# TopLevel.net
KiCad netlist of a schematic drawn in Altium Designer
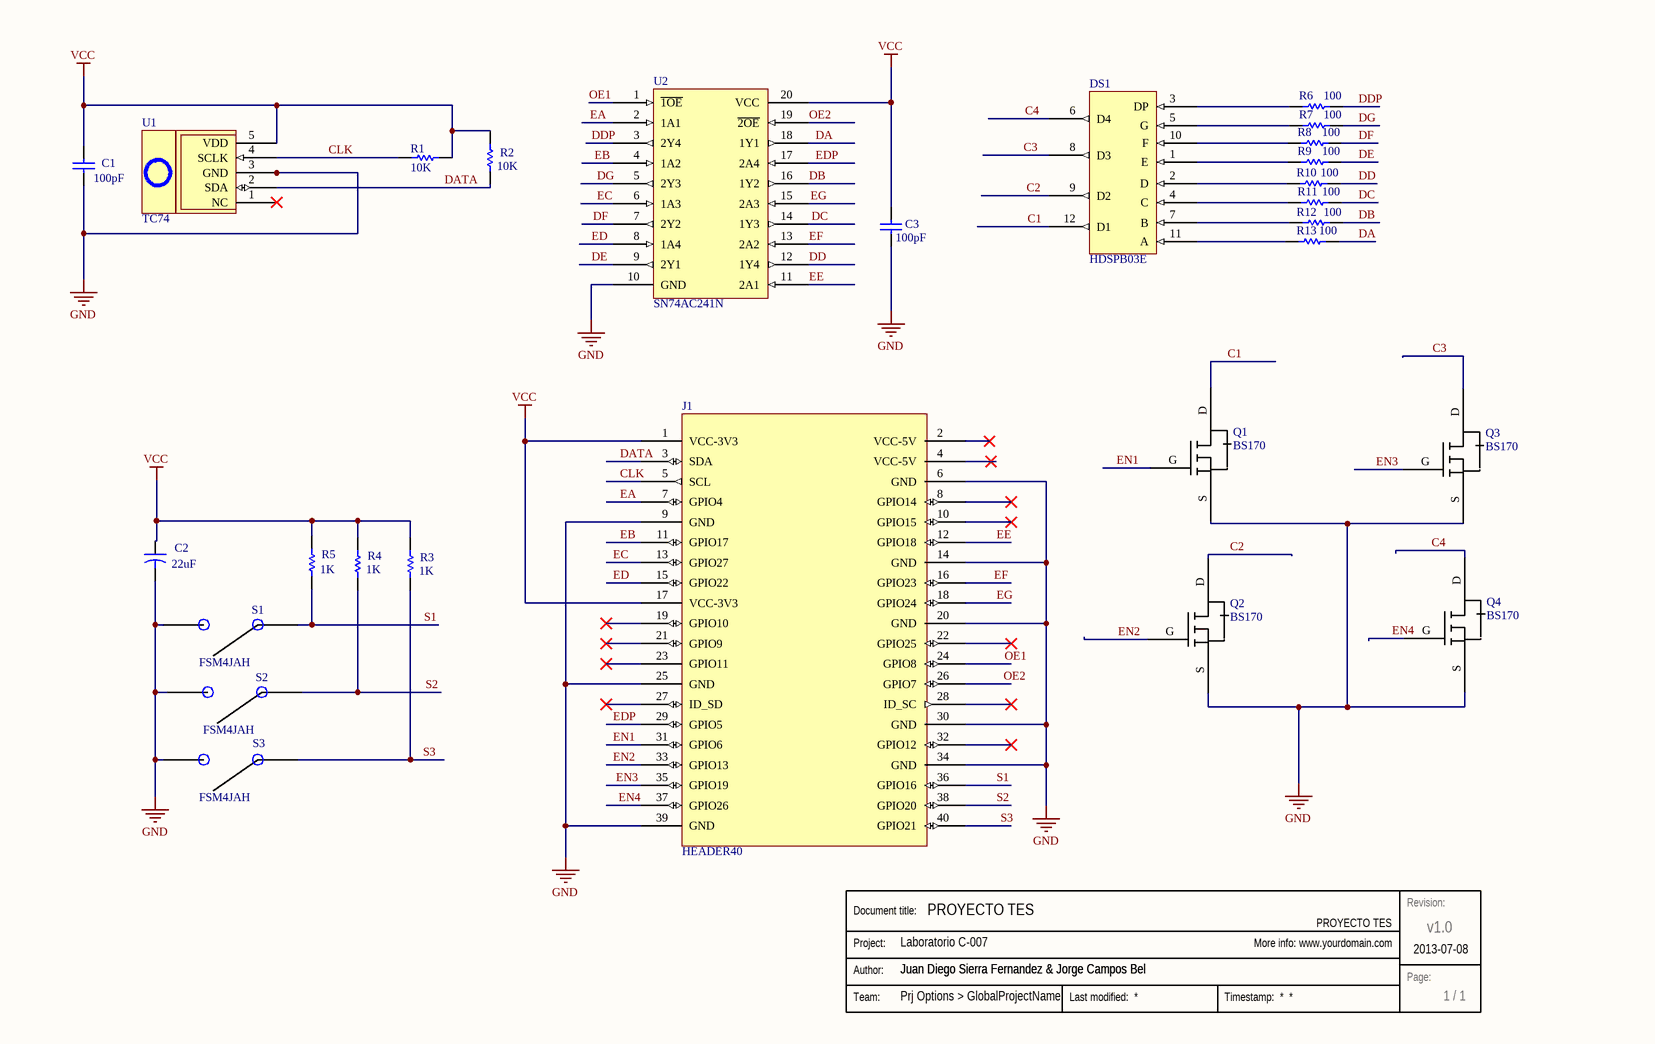
[diagram p0: TopLevel.SchDoc]

(export (version "E")
  (design (tool "Eeschema 10.0.6"))
  (components
    (comp (ref "C1")
      (value "100pF")
      (footprint "RAD-0.3")
      (description "Capacitor")
      (fields (field (name "Comment") "Cap") (field (name "PUBLISHER") "Altium Limited"))
      (libsource (lib "EM") (part "Cap"))
    )
    (comp (ref "C2")
      (value "22uF")
      (footprint "CAPR5-4X5")
      (description "Capacitor")
      (fields (field (name "Comment") "Cap2") (field (name "PUBLISHER") "Altium Limited"))
      (libsource (lib "EM") (part "Cap2"))
    )
    (comp (ref "C3")
      (value "100pF")
      (footprint "RAD-0.3")
      (description "Capacitor")
      (fields (field (name "Comment") "Cap") (field (name "PUBLISHER") "Altium Limited"))
      (libsource (lib "EM") (part "Cap"))
    )
    (comp (ref "DS1")
      (value "HDSPB03E")
      (footprint "DISPLAY")
      (description "Display")
      (libsource (lib "EM") (part "HDSPB03E"))
    )
    (comp (ref "J1")
      (value "HEADER40")
      (footprint "DIP40")
      (description "Header")
      (libsource (lib "EM") (part "HEADER40"))
    )
    (comp (ref "Q1")
      (value "BS170")
      (footprint "MOSFET")
      (description "Mosfet")
      (libsource (lib "EM") (part "BS170"))
    )
    (comp (ref "Q2")
      (value "BS170")
      (footprint "MOSFET")
      (description "Mosfet")
      (libsource (lib "EM") (part "BS170"))
    )
    (comp (ref "Q3")
      (value "BS170")
      (footprint "MOSFET")
      (description "Mosfet")
      (libsource (lib "EM") (part "BS170"))
    )
    (comp (ref "Q4")
      (value "BS170")
      (footprint "MOSFET")
      (description "Mosfet")
      (libsource (lib "EM") (part "BS170"))
    )
    (comp (ref "R1")
      (value "10K")
      (footprint "AXIAL-0.3")
      (description "Resistor")
      (fields (field (name "Comment") "Res1") (field (name "PUBLISHER") "Altium Limited"))
      (libsource (lib "EM") (part "Res1"))
    )
    (comp (ref "R2")
      (value "10K")
      (footprint "AXIAL-0.3")
      (description "Resistor")
      (fields (field (name "Comment") "Res1") (field (name "PUBLISHER") "Altium Limited"))
      (libsource (lib "EM") (part "Res1"))
    )
    (comp (ref "R3")
      (value "1K")
      (footprint "AXIAL-0.3")
      (description "Resistor")
      (fields (field (name "Comment") "Res1") (field (name "PUBLISHER") "Altium Limited"))
      (libsource (lib "EM") (part "Res1"))
    )
    (comp (ref "R4")
      (value "1K")
      (footprint "AXIAL-0.3")
      (description "Resistor")
      (fields (field (name "Comment") "Res1") (field (name "PUBLISHER") "Altium Limited"))
      (libsource (lib "EM") (part "Res1"))
    )
    (comp (ref "R5")
      (value "1K")
      (footprint "AXIAL-0.3")
      (description "Resistor")
      (fields (field (name "Comment") "Res1") (field (name "PUBLISHER") "Altium Limited"))
      (libsource (lib "EM") (part "Res1"))
    )
    (comp (ref "R6")
      (value "100")
      (footprint "AXIAL-0.3")
      (description "Resistor")
      (fields (field (name "Comment") "Res1") (field (name "PUBLISHER") "Altium Limited"))
      (libsource (lib "EM") (part "Res1"))
    )
    (comp (ref "R7")
      (value "100")
      (footprint "AXIAL-0.3")
      (description "Resistor")
      (fields (field (name "Comment") "Res1") (field (name "PUBLISHER") "Altium Limited"))
      (libsource (lib "EM") (part "Res1"))
    )
    (comp (ref "R8")
      (value "100")
      (footprint "AXIAL-0.3")
      (description "Resistor")
      (fields (field (name "Comment") "Res1") (field (name "PUBLISHER") "Altium Limited"))
      (libsource (lib "EM") (part "Res1"))
    )
    (comp (ref "R9")
      (value "100")
      (footprint "AXIAL-0.3")
      (description "Resistor")
      (fields (field (name "Comment") "Res1") (field (name "PUBLISHER") "Altium Limited"))
      (libsource (lib "EM") (part "Res1"))
    )
    (comp (ref "R10")
      (value "100")
      (footprint "AXIAL-0.3")
      (description "Resistor")
      (fields (field (name "Comment") "Res1") (field (name "PUBLISHER") "Altium Limited"))
      (libsource (lib "EM") (part "Res1"))
    )
    (comp (ref "R11")
      (value "100")
      (footprint "AXIAL-0.3")
      (description "Resistor")
      (fields (field (name "Comment") "Res1") (field (name "PUBLISHER") "Altium Limited"))
      (libsource (lib "EM") (part "Res1"))
    )
    (comp (ref "R12")
      (value "100")
      (footprint "AXIAL-0.3")
      (description "Resistor")
      (fields (field (name "Comment") "Res1") (field (name "PUBLISHER") "Altium Limited"))
      (libsource (lib "EM") (part "Res1"))
    )
    (comp (ref "R13")
      (value "100")
      (footprint "AXIAL-0.3")
      (description "Resistor")
      (fields (field (name "Comment") "Res1") (field (name "PUBLISHER") "Altium Limited"))
      (libsource (lib "EM") (part "Res1"))
    )
    (comp (ref "S1")
      (value "FSM4JAH")
      (footprint "SPST")
      (description "Switch")
      (libsource (lib "EM") (part "FSM4JAH"))
    )
    (comp (ref "S2")
      (value "FSM4JAH")
      (footprint "SPST")
      (description "Switch")
      (libsource (lib "EM") (part "FSM4JAH"))
    )
    (comp (ref "S3")
      (value "FSM4JAH")
      (footprint "SPST")
      (description "Switch")
      (libsource (lib "EM") (part "FSM4JAH"))
    )
    (comp (ref "Stamp") (value "Stamp") (libsource (lib "ShieldsLib") (part "Stamp")))
    (comp (ref "U1")
      (value "TC74")
      (footprint "T0220")
      (description "Sensor")
      (libsource (lib "EM") (part "TC74"))
    )
    (comp (ref "U2")
      (value "SN74AC241N")
      (footprint "SN74")
      (description "Driver")
      (libsource (lib "EM") (part "SN74AC241N"))
    )
  )
  (nets
    (net (code "1") (name "/C1") (class "Default")
      (node (ref "DS1") (pin "12") (pinfunction "D1_12") (pintype "output"))
      (node (ref "Q1") (pin "D") (pinfunction "Drain_D") (pintype "passive"))
    )
    (net (code "2") (name "/C2") (class "Default")
      (node (ref "DS1") (pin "9") (pinfunction "D2_9") (pintype "output"))
      (node (ref "Q2") (pin "D") (pinfunction "Drain_D") (pintype "passive"))
    )
    (net (code "3") (name "/C3") (class "Default")
      (node (ref "DS1") (pin "8") (pinfunction "D3_8") (pintype "output"))
      (node (ref "Q3") (pin "D") (pinfunction "Drain_D") (pintype "passive"))
    )
    (net (code "4") (name "/C4") (class "Default")
      (node (ref "DS1") (pin "6") (pinfunction "D4_6") (pintype "output"))
      (node (ref "Q4") (pin "D") (pinfunction "Drain_D") (pintype "passive"))
    )
    (net (code "5") (name "/CLK") (class "Default")
      (node (ref "J1") (pin "5") (pinfunction "SCL_5") (pintype "output"))
      (node (ref "R1") (pin "2") (pinfunction "2_2") (pintype "passive"))
      (node (ref "U1") (pin "4") (pinfunction "SCLK_4") (pintype "input"))
    )
    (net (code "6") (name "/DA") (class "Default")
      (node (ref "R13") (pin "2") (pinfunction "2_2") (pintype "passive"))
      (node (ref "U2") (pin "18") (pinfunction "1Y1_18") (pintype "output"))
    )
    (net (code "7") (name "/DATA") (class "Default")
      (node (ref "J1") (pin "3") (pinfunction "SDA_3") (pintype "bidirectional"))
      (node (ref "R2") (pin "1") (pinfunction "1_1") (pintype "passive"))
      (node (ref "U1") (pin "2") (pinfunction "SDA_2") (pintype "bidirectional"))
    )
    (net (code "8") (name "/DB") (class "Default")
      (node (ref "R12") (pin "2") (pinfunction "2_2") (pintype "passive"))
      (node (ref "U2") (pin "16") (pinfunction "1Y2_16") (pintype "output"))
    )
    (net (code "9") (name "/DC") (class "Default")
      (node (ref "R11") (pin "2") (pinfunction "2_2") (pintype "passive"))
      (node (ref "U2") (pin "14") (pinfunction "1Y3_14") (pintype "output"))
    )
    (net (code "10") (name "/DD") (class "Default")
      (node (ref "R10") (pin "2") (pinfunction "2_2") (pintype "passive"))
      (node (ref "U2") (pin "12") (pinfunction "1Y4_12") (pintype "output"))
    )
    (net (code "11") (name "/DDP") (class "Default")
      (node (ref "R6") (pin "2") (pinfunction "2_2") (pintype "passive"))
      (node (ref "U2") (pin "3") (pinfunction "2Y4_3") (pintype "output"))
    )
    (net (code "12") (name "/DE") (class "Default")
      (node (ref "R9") (pin "2") (pinfunction "2_2") (pintype "passive"))
      (node (ref "U2") (pin "9") (pinfunction "2Y1_9") (pintype "output"))
    )
    (net (code "13") (name "/DF") (class "Default")
      (node (ref "R8") (pin "2") (pinfunction "2_2") (pintype "passive"))
      (node (ref "U2") (pin "7") (pinfunction "2Y2_7") (pintype "output"))
    )
    (net (code "14") (name "/DG") (class "Default")
      (node (ref "R7") (pin "2") (pinfunction "2_2") (pintype "passive"))
      (node (ref "U2") (pin "5") (pinfunction "2Y3_5") (pintype "output"))
    )
    (net (code "15") (name "/EA") (class "Default")
      (node (ref "J1") (pin "7") (pinfunction "GPIO4_7") (pintype "bidirectional"))
      (node (ref "U2") (pin "2") (pinfunction "1A1_2") (pintype "input"))
    )
    (net (code "16") (name "/EB") (class "Default")
      (node (ref "J1") (pin "11") (pinfunction "GPIO17_11") (pintype "bidirectional"))
      (node (ref "U2") (pin "4") (pinfunction "1A2_4") (pintype "input"))
    )
    (net (code "17") (name "/EC") (class "Default")
      (node (ref "J1") (pin "13") (pinfunction "GPIO27_13") (pintype "bidirectional"))
      (node (ref "U2") (pin "6") (pinfunction "1A3_6") (pintype "input"))
    )
    (net (code "18") (name "/ED") (class "Default")
      (node (ref "J1") (pin "15") (pinfunction "GPIO22_15") (pintype "bidirectional"))
      (node (ref "U2") (pin "8") (pinfunction "1A4_8") (pintype "input"))
    )
    (net (code "19") (name "/EDP") (class "Default")
      (node (ref "J1") (pin "29") (pinfunction "GPIO5_29") (pintype "bidirectional"))
      (node (ref "U2") (pin "17") (pinfunction "2A4_17") (pintype "input"))
    )
    (net (code "20") (name "/EE") (class "Default")
      (node (ref "J1") (pin "12") (pinfunction "GPIO18_12") (pintype "bidirectional"))
      (node (ref "U2") (pin "11") (pinfunction "2A1_11") (pintype "input"))
    )
    (net (code "21") (name "/EF") (class "Default")
      (node (ref "J1") (pin "16") (pinfunction "GPIO23_16") (pintype "bidirectional"))
      (node (ref "U2") (pin "13") (pinfunction "2A2_13") (pintype "input"))
    )
    (net (code "22") (name "/EG") (class "Default")
      (node (ref "J1") (pin "18") (pinfunction "GPIO24_18") (pintype "bidirectional"))
      (node (ref "U2") (pin "15") (pinfunction "2A3_15") (pintype "input"))
    )
    (net (code "23") (name "/EN1") (class "Default")
      (node (ref "J1") (pin "31") (pinfunction "GPIO6_31") (pintype "bidirectional"))
      (node (ref "Q1") (pin "G") (pinfunction "Gate_G") (pintype "passive"))
    )
    (net (code "24") (name "/EN2") (class "Default")
      (node (ref "J1") (pin "33") (pinfunction "GPIO13_33") (pintype "bidirectional"))
      (node (ref "Q2") (pin "G") (pinfunction "Gate_G") (pintype "passive"))
    )
    (net (code "25") (name "/EN3") (class "Default")
      (node (ref "J1") (pin "35") (pinfunction "GPIO19_35") (pintype "bidirectional"))
      (node (ref "Q3") (pin "G") (pinfunction "Gate_G") (pintype "passive"))
    )
    (net (code "26") (name "/EN4") (class "Default")
      (node (ref "J1") (pin "37") (pinfunction "GPIO26_37") (pintype "bidirectional"))
      (node (ref "Q4") (pin "G") (pinfunction "Gate_G") (pintype "passive"))
    )
    (net (code "27") (name "/OE1") (class "Default")
      (node (ref "J1") (pin "24") (pinfunction "GPIO8_24") (pintype "bidirectional"))
      (node (ref "U2") (pin "1") (pinfunction "~{1OE}_1") (pintype "input"))
    )
    (net (code "28") (name "/OE2") (class "Default")
      (node (ref "J1") (pin "26") (pinfunction "GPIO7_26") (pintype "bidirectional"))
      (node (ref "U2") (pin "19") (pinfunction "~{2OE}_19") (pintype "input"))
    )
    (net (code "29") (name "/S1") (class "Default")
      (node (ref "J1") (pin "36") (pinfunction "GPIO16_36") (pintype "bidirectional"))
      (node (ref "R5") (pin "1") (pinfunction "1_1") (pintype "passive"))
      (node (ref "S1") (pin "1") (pinfunction "1_1") (pintype "passive"))
    )
    (net (code "30") (name "/S2") (class "Default")
      (node (ref "J1") (pin "38") (pinfunction "GPIO20_38") (pintype "bidirectional"))
      (node (ref "R4") (pin "1") (pinfunction "1_1") (pintype "passive"))
      (node (ref "S2") (pin "1") (pinfunction "1_1") (pintype "passive"))
    )
    (net (code "31") (name "/S3") (class "Default")
      (node (ref "J1") (pin "40") (pinfunction "GPIO21_40") (pintype "bidirectional"))
      (node (ref "R3") (pin "1") (pinfunction "1_1") (pintype "passive"))
      (node (ref "S3") (pin "1") (pinfunction "1_1") (pintype "passive"))
    )
    (net (code "32") (name "GND") (class "Default")
      (node (ref "C1") (pin "1") (pinfunction "1_1") (pintype "passive"))
      (node (ref "C2") (pin "2") (pinfunction "2_2") (pintype "passive"))
      (node (ref "C3") (pin "1") (pinfunction "1_1") (pintype "passive"))
      (node (ref "J1") (pin "14") (pinfunction "GND_14") (pintype "passive"))
      (node (ref "J1") (pin "20") (pinfunction "GND_20") (pintype "passive"))
      (node (ref "J1") (pin "25") (pinfunction "GND_25") (pintype "passive"))
      (node (ref "J1") (pin "30") (pinfunction "GND_30") (pintype "passive"))
      (node (ref "J1") (pin "34") (pinfunction "GND_34") (pintype "passive"))
      (node (ref "J1") (pin "39") (pinfunction "GND_39") (pintype "passive"))
      (node (ref "J1") (pin "6") (pinfunction "GND_6") (pintype "passive"))
      (node (ref "J1") (pin "9") (pinfunction "GND_9") (pintype "passive"))
      (node (ref "Q1") (pin "S") (pinfunction "Source_S") (pintype "passive"))
      (node (ref "Q2") (pin "S") (pinfunction "Source_S") (pintype "passive"))
      (node (ref "Q3") (pin "S") (pinfunction "Source_S") (pintype "passive"))
      (node (ref "Q4") (pin "S") (pinfunction "Source_S") (pintype "passive"))
      (node (ref "S1") (pin "2") (pinfunction "2_2") (pintype "passive"))
      (node (ref "S2") (pin "2") (pinfunction "2_2") (pintype "passive"))
      (node (ref "S3") (pin "2") (pinfunction "2_2") (pintype "passive"))
      (node (ref "U1") (pin "3") (pinfunction "GND_3") (pintype "passive"))
      (node (ref "U2") (pin "10") (pinfunction "GND_10") (pintype "power_in"))
    )
    (net (code "33") (name "Net-(DS1-A)") (class "Default")
      (node (ref "DS1") (pin "11") (pinfunction "A_11") (pintype "input"))
      (node (ref "R13") (pin "1") (pinfunction "1_1") (pintype "passive"))
    )
    (net (code "34") (name "Net-(DS1-B)") (class "Default")
      (node (ref "DS1") (pin "7") (pinfunction "B_7") (pintype "input"))
      (node (ref "R12") (pin "1") (pinfunction "1_1") (pintype "passive"))
    )
    (net (code "35") (name "Net-(DS1-C)") (class "Default")
      (node (ref "DS1") (pin "4") (pinfunction "C_4") (pintype "input"))
      (node (ref "R11") (pin "1") (pinfunction "1_1") (pintype "passive"))
    )
    (net (code "36") (name "Net-(DS1-D)") (class "Default")
      (node (ref "DS1") (pin "2") (pinfunction "D_2") (pintype "input"))
      (node (ref "R10") (pin "1") (pinfunction "1_1") (pintype "passive"))
    )
    (net (code "37") (name "Net-(DS1-DP)") (class "Default")
      (node (ref "DS1") (pin "3") (pinfunction "DP_3") (pintype "input"))
      (node (ref "R6") (pin "1") (pinfunction "1_1") (pintype "passive"))
    )
    (net (code "38") (name "Net-(DS1-E)") (class "Default")
      (node (ref "DS1") (pin "1") (pinfunction "E_1") (pintype "input"))
      (node (ref "R9") (pin "1") (pinfunction "1_1") (pintype "passive"))
    )
    (net (code "39") (name "Net-(DS1-F)") (class "Default")
      (node (ref "DS1") (pin "10") (pinfunction "F_10") (pintype "input"))
      (node (ref "R8") (pin "1") (pinfunction "1_1") (pintype "passive"))
    )
    (net (code "40") (name "Net-(DS1-G)") (class "Default")
      (node (ref "DS1") (pin "5") (pinfunction "G_5") (pintype "input"))
      (node (ref "R7") (pin "1") (pinfunction "1_1") (pintype "passive"))
    )
    (net (code "41") (name "VCC") (class "Default")
      (node (ref "C1") (pin "2") (pinfunction "2_2") (pintype "passive"))
      (node (ref "C2") (pin "1") (pinfunction "1_1") (pintype "passive"))
      (node (ref "C3") (pin "2") (pinfunction "2_2") (pintype "passive"))
      (node (ref "J1") (pin "1") (pinfunction "VCC-3V3_1") (pintype "passive"))
      (node (ref "J1") (pin "17") (pinfunction "VCC-3V3_17") (pintype "passive"))
      (node (ref "R1") (pin "1") (pinfunction "1_1") (pintype "passive"))
      (node (ref "R2") (pin "2") (pinfunction "2_2") (pintype "passive"))
      (node (ref "R3") (pin "2") (pinfunction "2_2") (pintype "passive"))
      (node (ref "R4") (pin "2") (pinfunction "2_2") (pintype "passive"))
      (node (ref "R5") (pin "2") (pinfunction "2_2") (pintype "passive"))
      (node (ref "U1") (pin "5") (pinfunction "VDD_5") (pintype "passive"))
      (node (ref "U2") (pin "20") (pinfunction "VCC_20") (pintype "power_in"))
    )
    (net (code "42") (name "unconnected-(J1-GPIO9-Pad21)") (class "Default")
      (node (ref "J1") (pin "21") (pinfunction "GPIO9_21") (pintype "bidirectional+no_connect"))
    )
    (net (code "43") (name "unconnected-(J1-GPIO10-Pad19)") (class "Default")
      (node (ref "J1") (pin "19") (pinfunction "GPIO10_19") (pintype "bidirectional+no_connect"))
    )
    (net (code "44") (name "unconnected-(J1-GPIO11-Pad23)") (class "Default")
      (node (ref "J1") (pin "23") (pinfunction "GPIO11_23") (pintype "passive+no_connect"))
    )
    (net (code "45") (name "unconnected-(J1-GPIO12-Pad32)") (class "Default")
      (node (ref "J1") (pin "32") (pinfunction "GPIO12_32") (pintype "bidirectional+no_connect"))
    )
    (net (code "46") (name "unconnected-(J1-GPIO14-Pad8)") (class "Default")
      (node (ref "J1") (pin "8") (pinfunction "GPIO14_8") (pintype "bidirectional+no_connect"))
    )
    (net (code "47") (name "unconnected-(J1-GPIO15-Pad10)") (class "Default")
      (node (ref "J1") (pin "10") (pinfunction "GPIO15_10") (pintype "bidirectional+no_connect"))
    )
    (net (code "48") (name "unconnected-(J1-GPIO25-Pad22)") (class "Default")
      (node (ref "J1") (pin "22") (pinfunction "GPIO25_22") (pintype "bidirectional+no_connect"))
    )
    (net (code "49") (name "unconnected-(J1-ID_SC-Pad28)") (class "Default")
      (node (ref "J1") (pin "28") (pinfunction "ID_SC_28") (pintype "output+no_connect"))
    )
    (net (code "50") (name "unconnected-(J1-ID_SD-Pad27)") (class "Default")
      (node (ref "J1") (pin "27") (pinfunction "ID_SD_27") (pintype "bidirectional+no_connect"))
    )
    (net (code "51") (name "unconnected-(J1-VCC-5V-Pad2)") (class "Default")
      (node (ref "J1") (pin "2") (pinfunction "VCC-5V_2") (pintype "passive+no_connect"))
    )
    (net (code "52") (name "unconnected-(J1-VCC-5V-Pad4)") (class "Default")
      (node (ref "J1") (pin "4") (pinfunction "VCC-5V_4") (pintype "passive"))
    )
    (net (code "53") (name "unconnected-(U1-NC-Pad1)") (class "Default")
      (node (ref "U1") (pin "1") (pinfunction "NC_1") (pintype "passive+no_connect"))
    )
  )
)
